# S7CAS-PLEIADES-CARTE-MERE_P07_DDR.net
KiCad netlist of a schematic drawn in Altium Designer
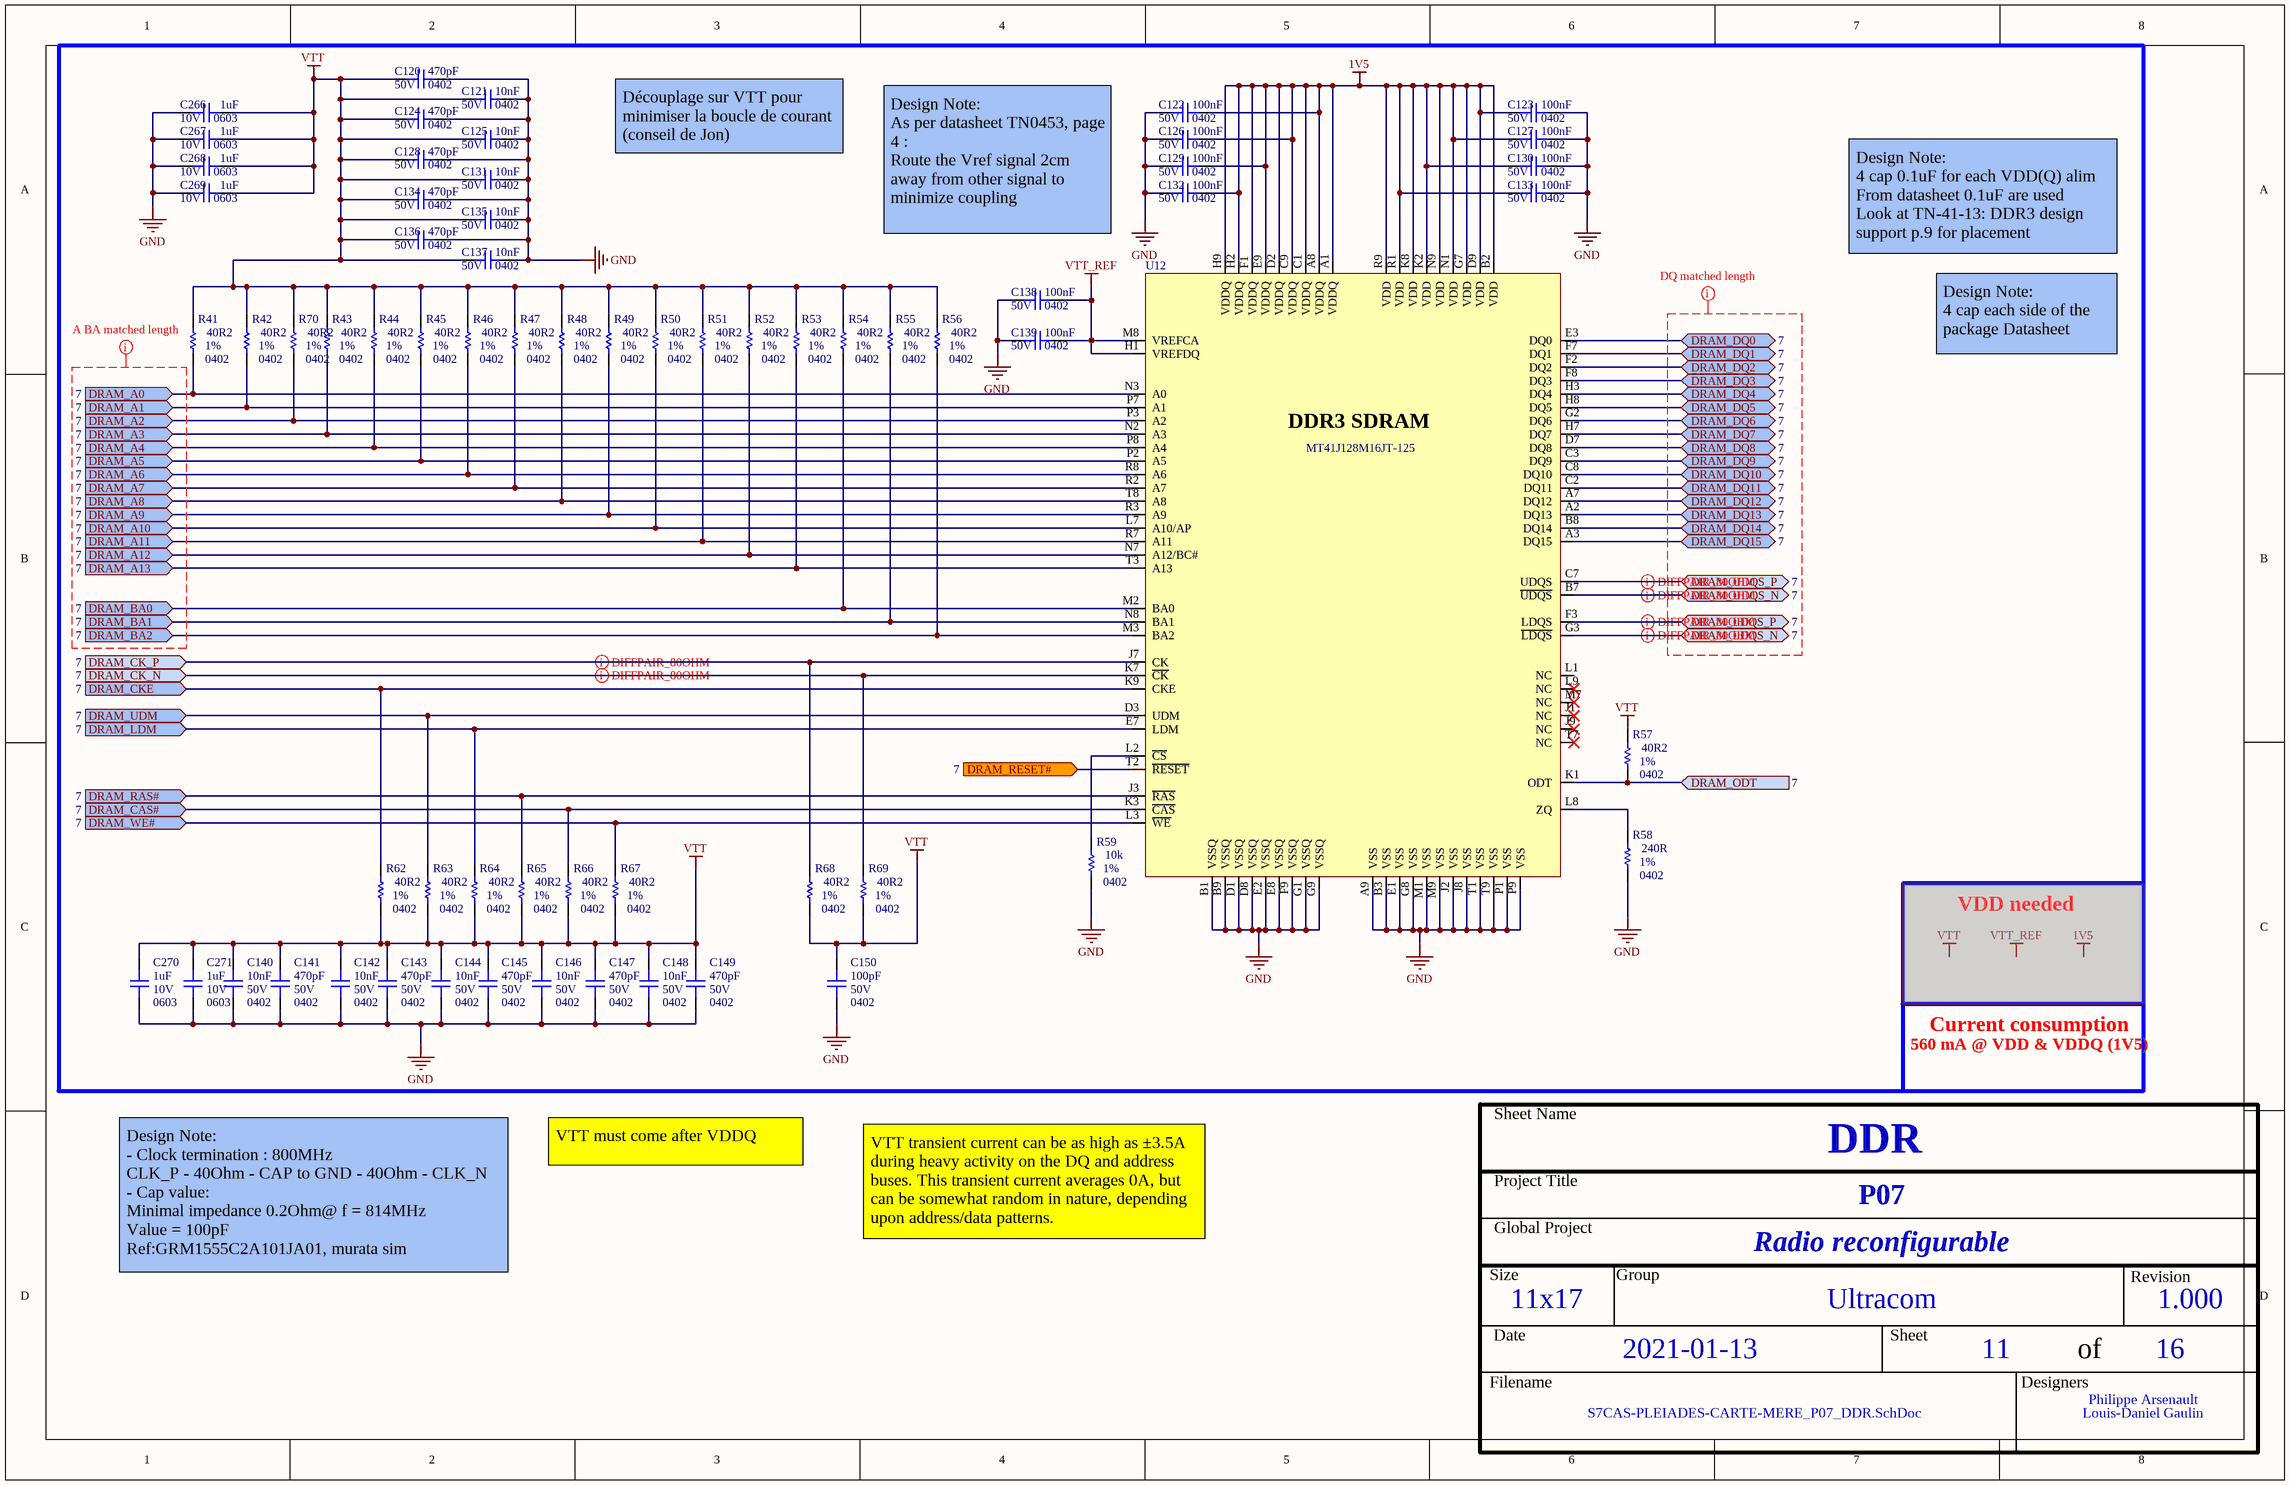
[diagram p0: S7CAS-PLEIADES-CARTE-MERE_P07_DDR.SchDoc]

(export (version "E")
  (design (tool "Eeschema 10.0.6"))
  (components
    (comp (ref "C120")
      (value "470pF")
      (footprint "CAP_0402")
      (description "CAP - 0402")
      (fields
        (field (name "VOLTAGE") "50V")
        (field (name "PACKAGE") "0402")
        (field (name "CREATEDBY") "Jonathan Bouchard")
      )
      (libsource (lib "S7CAS_LIB2021") (part "CAP - 0402"))
    )
    (comp (ref "C121")
      (value "10nF")
      (footprint "CAP_0402")
      (description "CAP - 0402")
      (fields
        (field (name "VOLTAGE") "50V")
        (field (name "PACKAGE") "0402")
        (field (name "CREATEDBY") "Jonathan Bouchard")
      )
      (libsource (lib "S7CAS_LIB2021") (part "CAP - 0402"))
    )
    (comp (ref "C122")
      (value "100nF")
      (footprint "CAP_0402")
      (description "CAP - 0402")
      (fields
        (field (name "VOLTAGE") "50V")
        (field (name "PACKAGE") "0402")
        (field (name "CREATEDBY") "Jonathan Bouchard")
      )
      (libsource (lib "S7CAS_LIB2021") (part "CAP - 0402"))
    )
    (comp (ref "C123")
      (value "100nF")
      (footprint "CAP_0402")
      (description "CAP - 0402")
      (fields
        (field (name "VOLTAGE") "50V")
        (field (name "PACKAGE") "0402")
        (field (name "CREATEDBY") "Jonathan Bouchard")
      )
      (libsource (lib "S7CAS_LIB2021") (part "CAP - 0402"))
    )
    (comp (ref "C124")
      (value "470pF")
      (footprint "CAP_0402")
      (description "CAP - 0402")
      (fields
        (field (name "VOLTAGE") "50V")
        (field (name "PACKAGE") "0402")
        (field (name "CREATEDBY") "Jonathan Bouchard")
      )
      (libsource (lib "S7CAS_LIB2021") (part "CAP - 0402"))
    )
    (comp (ref "C125")
      (value "10nF")
      (footprint "CAP_0402")
      (description "CAP - 0402")
      (fields
        (field (name "VOLTAGE") "50V")
        (field (name "PACKAGE") "0402")
        (field (name "CREATEDBY") "Jonathan Bouchard")
      )
      (libsource (lib "S7CAS_LIB2021") (part "CAP - 0402"))
    )
    (comp (ref "C126")
      (value "100nF")
      (footprint "CAP_0402")
      (description "CAP - 0402")
      (fields
        (field (name "VOLTAGE") "50V")
        (field (name "PACKAGE") "0402")
        (field (name "CREATEDBY") "Jonathan Bouchard")
      )
      (libsource (lib "S7CAS_LIB2021") (part "CAP - 0402"))
    )
    (comp (ref "C127")
      (value "100nF")
      (footprint "CAP_0402")
      (description "CAP - 0402")
      (fields
        (field (name "VOLTAGE") "50V")
        (field (name "PACKAGE") "0402")
        (field (name "CREATEDBY") "Jonathan Bouchard")
      )
      (libsource (lib "S7CAS_LIB2021") (part "CAP - 0402"))
    )
    (comp (ref "C128")
      (value "470pF")
      (footprint "CAP_0402")
      (description "CAP - 0402")
      (fields
        (field (name "VOLTAGE") "50V")
        (field (name "PACKAGE") "0402")
        (field (name "CREATEDBY") "Jonathan Bouchard")
      )
      (libsource (lib "S7CAS_LIB2021") (part "CAP - 0402"))
    )
    (comp (ref "C129")
      (value "100nF")
      (footprint "CAP_0402")
      (description "CAP - 0402")
      (fields
        (field (name "VOLTAGE") "50V")
        (field (name "PACKAGE") "0402")
        (field (name "CREATEDBY") "Jonathan Bouchard")
      )
      (libsource (lib "S7CAS_LIB2021") (part "CAP - 0402"))
    )
    (comp (ref "C130")
      (value "100nF")
      (footprint "CAP_0402")
      (description "CAP - 0402")
      (fields
        (field (name "VOLTAGE") "50V")
        (field (name "PACKAGE") "0402")
        (field (name "CREATEDBY") "Jonathan Bouchard")
      )
      (libsource (lib "S7CAS_LIB2021") (part "CAP - 0402"))
    )
    (comp (ref "C131")
      (value "10nF")
      (footprint "CAP_0402")
      (description "CAP - 0402")
      (fields
        (field (name "VOLTAGE") "50V")
        (field (name "PACKAGE") "0402")
        (field (name "CREATEDBY") "Jonathan Bouchard")
      )
      (libsource (lib "S7CAS_LIB2021") (part "CAP - 0402"))
    )
    (comp (ref "C132")
      (value "100nF")
      (footprint "CAP_0402")
      (description "CAP - 0402")
      (fields
        (field (name "VOLTAGE") "50V")
        (field (name "PACKAGE") "0402")
        (field (name "CREATEDBY") "Jonathan Bouchard")
      )
      (libsource (lib "S7CAS_LIB2021") (part "CAP - 0402"))
    )
    (comp (ref "C133")
      (value "100nF")
      (footprint "CAP_0402")
      (description "CAP - 0402")
      (fields
        (field (name "VOLTAGE") "50V")
        (field (name "PACKAGE") "0402")
        (field (name "CREATEDBY") "Jonathan Bouchard")
      )
      (libsource (lib "S7CAS_LIB2021") (part "CAP - 0402"))
    )
    (comp (ref "C134")
      (value "470pF")
      (footprint "CAP_0402")
      (description "CAP - 0402")
      (fields
        (field (name "VOLTAGE") "50V")
        (field (name "PACKAGE") "0402")
        (field (name "CREATEDBY") "Jonathan Bouchard")
      )
      (libsource (lib "S7CAS_LIB2021") (part "CAP - 0402"))
    )
    (comp (ref "C135")
      (value "10nF")
      (footprint "CAP_0402")
      (description "CAP - 0402")
      (fields
        (field (name "VOLTAGE") "50V")
        (field (name "PACKAGE") "0402")
        (field (name "CREATEDBY") "Jonathan Bouchard")
      )
      (libsource (lib "S7CAS_LIB2021") (part "CAP - 0402"))
    )
    (comp (ref "C136")
      (value "470pF")
      (footprint "CAP_0402")
      (description "CAP - 0402")
      (fields
        (field (name "VOLTAGE") "50V")
        (field (name "PACKAGE") "0402")
        (field (name "CREATEDBY") "Jonathan Bouchard")
      )
      (libsource (lib "S7CAS_LIB2021") (part "CAP - 0402"))
    )
    (comp (ref "C137")
      (value "10nF")
      (footprint "CAP_0402")
      (description "CAP - 0402")
      (fields
        (field (name "VOLTAGE") "50V")
        (field (name "PACKAGE") "0402")
        (field (name "CREATEDBY") "Jonathan Bouchard")
      )
      (libsource (lib "S7CAS_LIB2021") (part "CAP - 0402"))
    )
    (comp (ref "C138")
      (value "100nF")
      (footprint "CAP_0402")
      (description "CAP - 0402")
      (fields
        (field (name "VOLTAGE") "50V")
        (field (name "PACKAGE") "0402")
        (field (name "CREATEDBY") "Jonathan Bouchard")
      )
      (libsource (lib "S7CAS_LIB2021") (part "CAP - 0402"))
    )
    (comp (ref "C139")
      (value "100nF")
      (footprint "CAP_0402")
      (description "CAP - 0402")
      (fields
        (field (name "VOLTAGE") "50V")
        (field (name "PACKAGE") "0402")
        (field (name "CREATEDBY") "Jonathan Bouchard")
      )
      (libsource (lib "S7CAS_LIB2021") (part "CAP - 0402"))
    )
    (comp (ref "C140")
      (value "10nF")
      (footprint "CAP_0402")
      (description "CAP - 0402")
      (fields
        (field (name "VOLTAGE") "50V")
        (field (name "PACKAGE") "0402")
        (field (name "CREATEDBY") "Jonathan Bouchard")
      )
      (libsource (lib "S7CAS_LIB2021") (part "CAP - 0402"))
    )
    (comp (ref "C141")
      (value "470pF")
      (footprint "CAP_0402")
      (description "CAP - 0402")
      (fields
        (field (name "VOLTAGE") "50V")
        (field (name "PACKAGE") "0402")
        (field (name "CREATEDBY") "Jonathan Bouchard")
      )
      (libsource (lib "S7CAS_LIB2021") (part "CAP - 0402"))
    )
    (comp (ref "C142")
      (value "10nF")
      (footprint "CAP_0402")
      (description "CAP - 0402")
      (fields
        (field (name "VOLTAGE") "50V")
        (field (name "PACKAGE") "0402")
        (field (name "CREATEDBY") "Jonathan Bouchard")
      )
      (libsource (lib "S7CAS_LIB2021") (part "CAP - 0402"))
    )
    (comp (ref "C143")
      (value "470pF")
      (footprint "CAP_0402")
      (description "CAP - 0402")
      (fields
        (field (name "VOLTAGE") "50V")
        (field (name "PACKAGE") "0402")
        (field (name "CREATEDBY") "Jonathan Bouchard")
      )
      (libsource (lib "S7CAS_LIB2021") (part "CAP - 0402"))
    )
    (comp (ref "C144")
      (value "10nF")
      (footprint "CAP_0402")
      (description "CAP - 0402")
      (fields
        (field (name "VOLTAGE") "50V")
        (field (name "PACKAGE") "0402")
        (field (name "CREATEDBY") "Jonathan Bouchard")
      )
      (libsource (lib "S7CAS_LIB2021") (part "CAP - 0402"))
    )
    (comp (ref "C145")
      (value "470pF")
      (footprint "CAP_0402")
      (description "CAP - 0402")
      (fields
        (field (name "VOLTAGE") "50V")
        (field (name "PACKAGE") "0402")
        (field (name "CREATEDBY") "Jonathan Bouchard")
      )
      (libsource (lib "S7CAS_LIB2021") (part "CAP - 0402"))
    )
    (comp (ref "C146")
      (value "10nF")
      (footprint "CAP_0402")
      (description "CAP - 0402")
      (fields
        (field (name "VOLTAGE") "50V")
        (field (name "PACKAGE") "0402")
        (field (name "CREATEDBY") "Jonathan Bouchard")
      )
      (libsource (lib "S7CAS_LIB2021") (part "CAP - 0402"))
    )
    (comp (ref "C147")
      (value "470pF")
      (footprint "CAP_0402")
      (description "CAP - 0402")
      (fields
        (field (name "VOLTAGE") "50V")
        (field (name "PACKAGE") "0402")
        (field (name "CREATEDBY") "Jonathan Bouchard")
      )
      (libsource (lib "S7CAS_LIB2021") (part "CAP - 0402"))
    )
    (comp (ref "C148")
      (value "10nF")
      (footprint "CAP_0402")
      (description "CAP - 0402")
      (fields
        (field (name "VOLTAGE") "50V")
        (field (name "PACKAGE") "0402")
        (field (name "CREATEDBY") "Jonathan Bouchard")
      )
      (libsource (lib "S7CAS_LIB2021") (part "CAP - 0402"))
    )
    (comp (ref "C149")
      (value "470pF")
      (footprint "CAP_0402")
      (description "CAP - 0402")
      (fields
        (field (name "VOLTAGE") "50V")
        (field (name "PACKAGE") "0402")
        (field (name "CREATEDBY") "Jonathan Bouchard")
      )
      (libsource (lib "S7CAS_LIB2021") (part "CAP - 0402"))
    )
    (comp (ref "C150")
      (value "100pF")
      (footprint "CAP_0402")
      (description "CAP - 0402")
      (fields
        (field (name "VOLTAGE") "50V")
        (field (name "PACKAGE") "0402")
        (field (name "CREATEDBY") "Jonathan Bouchard")
      )
      (libsource (lib "S7CAS_LIB2021") (part "CAP - 0402"))
    )
    (comp (ref "C266")
      (value "1uF")
      (footprint "CAP_0603")
      (description "CAP - 0603")
      (fields
        (field (name "VOLTAGE") "10V")
        (field (name "PACKAGE") "0603")
        (field (name "CREATEDBY") "Jonathan Bouchard")
      )
      (libsource (lib "S7CAS_LIB2021") (part "CAP - 0603"))
    )
    (comp (ref "C267")
      (value "1uF")
      (footprint "CAP_0603")
      (description "CAP - 0603")
      (fields
        (field (name "VOLTAGE") "10V")
        (field (name "PACKAGE") "0603")
        (field (name "CREATEDBY") "Jonathan Bouchard")
      )
      (libsource (lib "S7CAS_LIB2021") (part "CAP - 0603"))
    )
    (comp (ref "C268")
      (value "1uF")
      (footprint "CAP_0603")
      (description "CAP - 0603")
      (fields
        (field (name "VOLTAGE") "10V")
        (field (name "PACKAGE") "0603")
        (field (name "CREATEDBY") "Jonathan Bouchard")
      )
      (libsource (lib "S7CAS_LIB2021") (part "CAP - 0603"))
    )
    (comp (ref "C269")
      (value "1uF")
      (footprint "CAP_0603")
      (description "CAP - 0603")
      (fields
        (field (name "VOLTAGE") "10V")
        (field (name "PACKAGE") "0603")
        (field (name "CREATEDBY") "Jonathan Bouchard")
      )
      (libsource (lib "S7CAS_LIB2021") (part "CAP - 0603"))
    )
    (comp (ref "C270")
      (value "1uF")
      (footprint "CAP_0603")
      (description "CAP - 0603")
      (fields
        (field (name "VOLTAGE") "10V")
        (field (name "PACKAGE") "0603")
        (field (name "CREATEDBY") "Jonathan Bouchard")
      )
      (libsource (lib "S7CAS_LIB2021") (part "CAP - 0603"))
    )
    (comp (ref "C271")
      (value "1uF")
      (footprint "CAP_0603")
      (description "CAP - 0603")
      (fields
        (field (name "VOLTAGE") "10V")
        (field (name "PACKAGE") "0603")
        (field (name "CREATEDBY") "Jonathan Bouchard")
      )
      (libsource (lib "S7CAS_LIB2021") (part "CAP - 0603"))
    )
    (comp (ref "R41")
      (value "40R2")
      (footprint "RES_0402")
      (description "RES - 0402")
      (fields
        (field (name "VOLTAGE") "50V")
        (field (name "POWER") "1/16W")
        (field (name "PACKAGE") "0402")
        (field (name "PRECISION") "1%")
        (field (name "CREATEDBY") "Jonathan Bouchard")
      )
      (libsource (lib "S7CAS_LIB2021") (part "RES - 0402"))
    )
    (comp (ref "R42")
      (value "40R2")
      (footprint "RES_0402")
      (description "RES - 0402")
      (fields
        (field (name "VOLTAGE") "50V")
        (field (name "POWER") "1/16W")
        (field (name "PACKAGE") "0402")
        (field (name "PRECISION") "1%")
        (field (name "CREATEDBY") "Jonathan Bouchard")
      )
      (libsource (lib "S7CAS_LIB2021") (part "RES - 0402"))
    )
    (comp (ref "R43")
      (value "40R2")
      (footprint "RES_0402")
      (description "RES - 0402")
      (fields
        (field (name "VOLTAGE") "50V")
        (field (name "POWER") "1/16W")
        (field (name "PACKAGE") "0402")
        (field (name "PRECISION") "1%")
        (field (name "CREATEDBY") "Jonathan Bouchard")
      )
      (libsource (lib "S7CAS_LIB2021") (part "RES - 0402"))
    )
    (comp (ref "R44")
      (value "40R2")
      (footprint "RES_0402")
      (description "RES - 0402")
      (fields
        (field (name "VOLTAGE") "50V")
        (field (name "POWER") "1/16W")
        (field (name "PACKAGE") "0402")
        (field (name "PRECISION") "1%")
        (field (name "CREATEDBY") "Jonathan Bouchard")
      )
      (libsource (lib "S7CAS_LIB2021") (part "RES - 0402"))
    )
    (comp (ref "R45")
      (value "40R2")
      (footprint "RES_0402")
      (description "RES - 0402")
      (fields
        (field (name "VOLTAGE") "50V")
        (field (name "POWER") "1/16W")
        (field (name "PACKAGE") "0402")
        (field (name "PRECISION") "1%")
        (field (name "CREATEDBY") "Jonathan Bouchard")
      )
      (libsource (lib "S7CAS_LIB2021") (part "RES - 0402"))
    )
    (comp (ref "R46")
      (value "40R2")
      (footprint "RES_0402")
      (description "RES - 0402")
      (fields
        (field (name "VOLTAGE") "50V")
        (field (name "POWER") "1/16W")
        (field (name "PACKAGE") "0402")
        (field (name "PRECISION") "1%")
        (field (name "CREATEDBY") "Jonathan Bouchard")
      )
      (libsource (lib "S7CAS_LIB2021") (part "RES - 0402"))
    )
    (comp (ref "R47")
      (value "40R2")
      (footprint "RES_0402")
      (description "RES - 0402")
      (fields
        (field (name "VOLTAGE") "50V")
        (field (name "POWER") "1/16W")
        (field (name "PACKAGE") "0402")
        (field (name "PRECISION") "1%")
        (field (name "CREATEDBY") "Jonathan Bouchard")
      )
      (libsource (lib "S7CAS_LIB2021") (part "RES - 0402"))
    )
    (comp (ref "R48")
      (value "40R2")
      (footprint "RES_0402")
      (description "RES - 0402")
      (fields
        (field (name "VOLTAGE") "50V")
        (field (name "POWER") "1/16W")
        (field (name "PACKAGE") "0402")
        (field (name "PRECISION") "1%")
        (field (name "CREATEDBY") "Jonathan Bouchard")
      )
      (libsource (lib "S7CAS_LIB2021") (part "RES - 0402"))
    )
    (comp (ref "R49")
      (value "40R2")
      (footprint "RES_0402")
      (description "RES - 0402")
      (fields
        (field (name "VOLTAGE") "50V")
        (field (name "POWER") "1/16W")
        (field (name "PACKAGE") "0402")
        (field (name "PRECISION") "1%")
        (field (name "CREATEDBY") "Jonathan Bouchard")
      )
      (libsource (lib "S7CAS_LIB2021") (part "RES - 0402"))
    )
    (comp (ref "R50")
      (value "40R2")
      (footprint "RES_0402")
      (description "RES - 0402")
      (fields
        (field (name "VOLTAGE") "50V")
        (field (name "POWER") "1/16W")
        (field (name "PACKAGE") "0402")
        (field (name "PRECISION") "1%")
        (field (name "CREATEDBY") "Jonathan Bouchard")
      )
      (libsource (lib "S7CAS_LIB2021") (part "RES - 0402"))
    )
    (comp (ref "R51")
      (value "40R2")
      (footprint "RES_0402")
      (description "RES - 0402")
      (fields
        (field (name "VOLTAGE") "50V")
        (field (name "POWER") "1/16W")
        (field (name "PACKAGE") "0402")
        (field (name "PRECISION") "1%")
        (field (name "CREATEDBY") "Jonathan Bouchard")
      )
      (libsource (lib "S7CAS_LIB2021") (part "RES - 0402"))
    )
    (comp (ref "R52")
      (value "40R2")
      (footprint "RES_0402")
      (description "RES - 0402")
      (fields
        (field (name "VOLTAGE") "50V")
        (field (name "POWER") "1/16W")
        (field (name "PACKAGE") "0402")
        (field (name "PRECISION") "1%")
        (field (name "CREATEDBY") "Jonathan Bouchard")
      )
      (libsource (lib "S7CAS_LIB2021") (part "RES - 0402"))
    )
    (comp (ref "R53")
      (value "40R2")
      (footprint "RES_0402")
      (description "RES - 0402")
      (fields
        (field (name "VOLTAGE") "50V")
        (field (name "POWER") "1/16W")
        (field (name "PACKAGE") "0402")
        (field (name "PRECISION") "1%")
        (field (name "CREATEDBY") "Jonathan Bouchard")
      )
      (libsource (lib "S7CAS_LIB2021") (part "RES - 0402"))
    )
    (comp (ref "R54")
      (value "40R2")
      (footprint "RES_0402")
      (description "RES - 0402")
      (fields
        (field (name "VOLTAGE") "50V")
        (field (name "POWER") "1/16W")
        (field (name "PACKAGE") "0402")
        (field (name "PRECISION") "1%")
        (field (name "CREATEDBY") "Jonathan Bouchard")
      )
      (libsource (lib "S7CAS_LIB2021") (part "RES - 0402"))
    )
    (comp (ref "R55")
      (value "40R2")
      (footprint "RES_0402")
      (description "RES - 0402")
      (fields
        (field (name "VOLTAGE") "50V")
        (field (name "POWER") "1/16W")
        (field (name "PACKAGE") "0402")
        (field (name "PRECISION") "1%")
        (field (name "CREATEDBY") "Jonathan Bouchard")
      )
      (libsource (lib "S7CAS_LIB2021") (part "RES - 0402"))
    )
    (comp (ref "R56")
      (value "40R2")
      (footprint "RES_0402")
      (description "RES - 0402")
      (fields
        (field (name "VOLTAGE") "50V")
        (field (name "POWER") "1/16W")
        (field (name "PACKAGE") "0402")
        (field (name "PRECISION") "1%")
        (field (name "CREATEDBY") "Jonathan Bouchard")
      )
      (libsource (lib "S7CAS_LIB2021") (part "RES - 0402"))
    )
    (comp (ref "R57")
      (value "40R2")
      (footprint "RES_0402")
      (description "RES - 0402")
      (fields
        (field (name "VOLTAGE") "50V")
        (field (name "POWER") "1/16W")
        (field (name "PACKAGE") "0402")
        (field (name "PRECISION") "1%")
        (field (name "CREATEDBY") "Jonathan Bouchard")
      )
      (libsource (lib "S7CAS_LIB2021") (part "RES - 0402"))
    )
    (comp (ref "R58")
      (value "240R")
      (footprint "RES_0402")
      (description "RES - 0402")
      (fields
        (field (name "VOLTAGE") "50V")
        (field (name "POWER") "1/16W")
        (field (name "PACKAGE") "0402")
        (field (name "PRECISION") "1%")
        (field (name "CREATEDBY") "Jonathan Bouchard")
      )
      (libsource (lib "S7CAS_LIB2021") (part "RES - 0402"))
    )
    (comp (ref "R59")
      (value "10k")
      (footprint "RES_0402")
      (description "RES - 0402")
      (fields
        (field (name "VOLTAGE") "50V")
        (field (name "POWER") "1/16W")
        (field (name "PACKAGE") "0402")
        (field (name "PRECISION") "1%")
        (field (name "CREATEDBY") "Jonathan Bouchard")
      )
      (libsource (lib "S7CAS_LIB2021") (part "RES - 0402"))
    )
    (comp (ref "R62")
      (value "40R2")
      (footprint "RES_0402")
      (description "RES - 0402")
      (fields
        (field (name "VOLTAGE") "50V")
        (field (name "POWER") "1/16W")
        (field (name "PACKAGE") "0402")
        (field (name "PRECISION") "1%")
        (field (name "CREATEDBY") "Jonathan Bouchard")
      )
      (libsource (lib "S7CAS_LIB2021") (part "RES - 0402"))
    )
    (comp (ref "R63")
      (value "40R2")
      (footprint "RES_0402")
      (description "RES - 0402")
      (fields
        (field (name "VOLTAGE") "50V")
        (field (name "POWER") "1/16W")
        (field (name "PACKAGE") "0402")
        (field (name "PRECISION") "1%")
        (field (name "CREATEDBY") "Jonathan Bouchard")
      )
      (libsource (lib "S7CAS_LIB2021") (part "RES - 0402"))
    )
    (comp (ref "R64")
      (value "40R2")
      (footprint "RES_0402")
      (description "RES - 0402")
      (fields
        (field (name "VOLTAGE") "50V")
        (field (name "POWER") "1/16W")
        (field (name "PACKAGE") "0402")
        (field (name "PRECISION") "1%")
        (field (name "CREATEDBY") "Jonathan Bouchard")
      )
      (libsource (lib "S7CAS_LIB2021") (part "RES - 0402"))
    )
    (comp (ref "R65")
      (value "40R2")
      (footprint "RES_0402")
      (description "RES - 0402")
      (fields
        (field (name "VOLTAGE") "50V")
        (field (name "POWER") "1/16W")
        (field (name "PACKAGE") "0402")
        (field (name "PRECISION") "1%")
        (field (name "CREATEDBY") "Jonathan Bouchard")
      )
      (libsource (lib "S7CAS_LIB2021") (part "RES - 0402"))
    )
    (comp (ref "R66")
      (value "40R2")
      (footprint "RES_0402")
      (description "RES - 0402")
      (fields
        (field (name "VOLTAGE") "50V")
        (field (name "POWER") "1/16W")
        (field (name "PACKAGE") "0402")
        (field (name "PRECISION") "1%")
        (field (name "CREATEDBY") "Jonathan Bouchard")
      )
      (libsource (lib "S7CAS_LIB2021") (part "RES - 0402"))
    )
    (comp (ref "R67")
      (value "40R2")
      (footprint "RES_0402")
      (description "RES - 0402")
      (fields
        (field (name "VOLTAGE") "50V")
        (field (name "POWER") "1/16W")
        (field (name "PACKAGE") "0402")
        (field (name "PRECISION") "1%")
        (field (name "CREATEDBY") "Jonathan Bouchard")
      )
      (libsource (lib "S7CAS_LIB2021") (part "RES - 0402"))
    )
    (comp (ref "R68")
      (value "40R2")
      (footprint "RES_0402")
      (description "RES - 0402")
      (fields
        (field (name "VOLTAGE") "50V")
        (field (name "POWER") "1/16W")
        (field (name "PACKAGE") "0402")
        (field (name "PRECISION") "1%")
        (field (name "CREATEDBY") "Jonathan Bouchard")
      )
      (libsource (lib "S7CAS_LIB2021") (part "RES - 0402"))
    )
    (comp (ref "R69")
      (value "40R2")
      (footprint "RES_0402")
      (description "RES - 0402")
      (fields
        (field (name "VOLTAGE") "50V")
        (field (name "POWER") "1/16W")
        (field (name "PACKAGE") "0402")
        (field (name "PRECISION") "1%")
        (field (name "CREATEDBY") "Jonathan Bouchard")
      )
      (libsource (lib "S7CAS_LIB2021") (part "RES - 0402"))
    )
    (comp (ref "R70")
      (value "40R2")
      (footprint "RES_0402")
      (description "RES - 0402")
      (fields
        (field (name "VOLTAGE") "50V")
        (field (name "POWER") "1/16W")
        (field (name "PACKAGE") "0402")
        (field (name "PRECISION") "1%")
        (field (name "CREATEDBY") "Jonathan Bouchard")
      )
      (libsource (lib "S7CAS_LIB2021") (part "RES - 0402"))
    )
    (comp (ref "U12")
      (value "MT41J128M16JT-125")
      (footprint "MEM_DDR3_MT41J128M16JT-125")
      (description "MEM - DDR3 SDRAM 2GBIT 800MHZ - TFBGA-96")
      (fields
        (field (name "VOLTAGE") "1.425 V ~ 1.575 V")
        (field (name "MFG") "Micrel")
        (field (name "CREATEDBY") "Jonathan Bouchard")
      )
      (libsource (lib "S7CAS_LIB2021") (part "MEM_DDR3_MT41J128M16JT-125{colon}K TR"))
    )
  )
  (nets
    (net (code "1") (name "/DRAM_A0") (class "Default")
      (node (ref "R41") (pin "1") (pinfunction "1_1") (pintype "passive"))
      (node (ref "U12") (pin "N3") (pinfunction "A0_N3") (pintype "passive"))
    )
    (net (code "2") (name "/DRAM_A1") (class "Default")
      (node (ref "R42") (pin "1") (pinfunction "1_1") (pintype "passive"))
      (node (ref "U12") (pin "P7") (pinfunction "A1_P7") (pintype "passive"))
    )
    (net (code "3") (name "/DRAM_A2") (class "Default")
      (node (ref "R70") (pin "1") (pinfunction "1_1") (pintype "passive"))
      (node (ref "U12") (pin "P3") (pinfunction "A2_P3") (pintype "passive"))
    )
    (net (code "4") (name "/DRAM_A3") (class "Default")
      (node (ref "R43") (pin "1") (pinfunction "1_1") (pintype "passive"))
      (node (ref "U12") (pin "N2") (pinfunction "A3_N2") (pintype "passive"))
    )
    (net (code "5") (name "/DRAM_A4") (class "Default")
      (node (ref "R44") (pin "1") (pinfunction "1_1") (pintype "passive"))
      (node (ref "U12") (pin "P8") (pinfunction "A4_P8") (pintype "passive"))
    )
    (net (code "6") (name "/DRAM_A5") (class "Default")
      (node (ref "R45") (pin "1") (pinfunction "1_1") (pintype "passive"))
      (node (ref "U12") (pin "P2") (pinfunction "A5_P2") (pintype "passive"))
    )
    (net (code "7") (name "/DRAM_A6") (class "Default")
      (node (ref "R46") (pin "1") (pinfunction "1_1") (pintype "passive"))
      (node (ref "U12") (pin "R8") (pinfunction "A6_R8") (pintype "passive"))
    )
    (net (code "8") (name "/DRAM_A7") (class "Default")
      (node (ref "R47") (pin "1") (pinfunction "1_1") (pintype "passive"))
      (node (ref "U12") (pin "R2") (pinfunction "A7_R2") (pintype "passive"))
    )
    (net (code "9") (name "/DRAM_A8") (class "Default")
      (node (ref "R48") (pin "1") (pinfunction "1_1") (pintype "passive"))
      (node (ref "U12") (pin "T8") (pinfunction "A8_T8") (pintype "passive"))
    )
    (net (code "10") (name "/DRAM_A9") (class "Default")
      (node (ref "R49") (pin "1") (pinfunction "1_1") (pintype "passive"))
      (node (ref "U12") (pin "R3") (pinfunction "A9_R3") (pintype "passive"))
    )
    (net (code "11") (name "/DRAM_A10") (class "Default")
      (node (ref "R50") (pin "1") (pinfunction "1_1") (pintype "passive"))
      (node (ref "U12") (pin "L7") (pinfunction "A10/AP_L7") (pintype "passive"))
    )
    (net (code "12") (name "/DRAM_A11") (class "Default")
      (node (ref "R51") (pin "1") (pinfunction "1_1") (pintype "passive"))
      (node (ref "U12") (pin "R7") (pinfunction "A11_R7") (pintype "passive"))
    )
    (net (code "13") (name "/DRAM_A12") (class "Default")
      (node (ref "R52") (pin "1") (pinfunction "1_1") (pintype "passive"))
      (node (ref "U12") (pin "N7") (pinfunction "A12/BC#_N7") (pintype "passive"))
    )
    (net (code "14") (name "/DRAM_A13") (class "Default")
      (node (ref "R53") (pin "1") (pinfunction "1_1") (pintype "passive"))
      (node (ref "U12") (pin "T3") (pinfunction "A13_T3") (pintype "passive"))
    )
    (net (code "15") (name "/DRAM_BA0") (class "Default")
      (node (ref "R54") (pin "1") (pinfunction "1_1") (pintype "passive"))
      (node (ref "U12") (pin "M2") (pinfunction "BA0_M2") (pintype "passive"))
    )
    (net (code "16") (name "/DRAM_BA1") (class "Default")
      (node (ref "R55") (pin "1") (pinfunction "1_1") (pintype "passive"))
      (node (ref "U12") (pin "N8") (pinfunction "BA1_N8") (pintype "passive"))
    )
    (net (code "17") (name "/DRAM_BA2") (class "Default")
      (node (ref "R56") (pin "1") (pinfunction "1_1") (pintype "passive"))
      (node (ref "U12") (pin "M3") (pinfunction "BA2_M3") (pintype "passive"))
    )
    (net (code "18") (name "/DRAM_CAS#") (class "Default")
      (node (ref "R66") (pin "2") (pinfunction "2_2") (pintype "passive"))
      (node (ref "U12") (pin "K3") (pinfunction "CAS_K3") (pintype "passive"))
    )
    (net (code "19") (name "/DRAM_CKE") (class "Default")
      (node (ref "R62") (pin "2") (pinfunction "2_2") (pintype "passive"))
      (node (ref "U12") (pin "K9") (pinfunction "CKE_K9") (pintype "passive"))
    )
    (net (code "20") (name "/DRAM_CK_N") (class "Default")
      (node (ref "R69") (pin "2") (pinfunction "2_2") (pintype "passive"))
      (node (ref "U12") (pin "K7") (pinfunction "CK_K7") (pintype "passive"))
    )
    (net (code "21") (name "/DRAM_CK_P") (class "Default")
      (node (ref "R68") (pin "2") (pinfunction "2_2") (pintype "passive"))
      (node (ref "U12") (pin "J7") (pinfunction "CK_J7") (pintype "passive"))
    )
    (net (code "22") (name "/DRAM_DQ0") (class "Default")
      (node (ref "U12") (pin "E3") (pinfunction "DQ0_E3") (pintype "passive"))
    )
    (net (code "23") (name "/DRAM_DQ1") (class "Default")
      (node (ref "U12") (pin "F7") (pinfunction "DQ1_F7") (pintype "passive"))
    )
    (net (code "24") (name "/DRAM_DQ2") (class "Default")
      (node (ref "U12") (pin "F2") (pinfunction "DQ2_F2") (pintype "passive"))
    )
    (net (code "25") (name "/DRAM_DQ3") (class "Default")
      (node (ref "U12") (pin "F8") (pinfunction "DQ3_F8") (pintype "passive"))
    )
    (net (code "26") (name "/DRAM_DQ4") (class "Default")
      (node (ref "U12") (pin "H3") (pinfunction "DQ4_H3") (pintype "passive"))
    )
    (net (code "27") (name "/DRAM_DQ5") (class "Default")
      (node (ref "U12") (pin "H8") (pinfunction "DQ5_H8") (pintype "passive"))
    )
    (net (code "28") (name "/DRAM_DQ6") (class "Default")
      (node (ref "U12") (pin "G2") (pinfunction "DQ6_G2") (pintype "passive"))
    )
    (net (code "29") (name "/DRAM_DQ7") (class "Default")
      (node (ref "U12") (pin "H7") (pinfunction "DQ7_H7") (pintype "passive"))
    )
    (net (code "30") (name "/DRAM_DQ8") (class "Default")
      (node (ref "U12") (pin "D7") (pinfunction "DQ8_D7") (pintype "passive"))
    )
    (net (code "31") (name "/DRAM_DQ9") (class "Default")
      (node (ref "U12") (pin "C3") (pinfunction "DQ9_C3") (pintype "passive"))
    )
    (net (code "32") (name "/DRAM_DQ10") (class "Default")
      (node (ref "U12") (pin "C8") (pinfunction "DQ10_C8") (pintype "passive"))
    )
    (net (code "33") (name "/DRAM_DQ11") (class "Default")
      (node (ref "U12") (pin "C2") (pinfunction "DQ11_C2") (pintype "passive"))
    )
    (net (code "34") (name "/DRAM_DQ12") (class "Default")
      (node (ref "U12") (pin "A7") (pinfunction "DQ12_A7") (pintype "passive"))
    )
    (net (code "35") (name "/DRAM_DQ13") (class "Default")
      (node (ref "U12") (pin "A2") (pinfunction "DQ13_A2") (pintype "passive"))
    )
    (net (code "36") (name "/DRAM_DQ14") (class "Default")
      (node (ref "U12") (pin "B8") (pinfunction "DQ14_B8") (pintype "passive"))
    )
    (net (code "37") (name "/DRAM_DQ15") (class "Default")
      (node (ref "U12") (pin "A3") (pinfunction "DQ15_A3") (pintype "passive"))
    )
    (net (code "38") (name "/DRAM_LDM") (class "Default")
      (node (ref "R64") (pin "2") (pinfunction "2_2") (pintype "passive"))
      (node (ref "U12") (pin "E7") (pinfunction "LDM_E7") (pintype "passive"))
    )
    (net (code "39") (name "/DRAM_LDQS_N") (class "Default")
      (node (ref "U12") (pin "G3") (pinfunction "LDQS_G3") (pintype "passive"))
    )
    (net (code "40") (name "/DRAM_LDQS_P") (class "Default")
      (node (ref "U12") (pin "F3") (pinfunction "LDQS_F3") (pintype "passive"))
    )
    (net (code "41") (name "/DRAM_ODT") (class "Default")
      (node (ref "R57") (pin "1") (pinfunction "1_1") (pintype "passive"))
      (node (ref "U12") (pin "K1") (pinfunction "ODT_K1") (pintype "passive"))
    )
    (net (code "42") (name "/DRAM_RAS#") (class "Default")
      (node (ref "R65") (pin "2") (pinfunction "2_2") (pintype "passive"))
      (node (ref "U12") (pin "J3") (pinfunction "RAS_J3") (pintype "passive"))
    )
    (net (code "43") (name "/DRAM_RESET#") (class "Default")
      (node (ref "U12") (pin "T2") (pinfunction "RESET_T2") (pintype "passive"))
    )
    (net (code "44") (name "/DRAM_UDM") (class "Default")
      (node (ref "R63") (pin "2") (pinfunction "2_2") (pintype "passive"))
      (node (ref "U12") (pin "D3") (pinfunction "UDM_D3") (pintype "passive"))
    )
    (net (code "45") (name "/DRAM_UDQS_N") (class "Default")
      (node (ref "U12") (pin "B7") (pinfunction "UDQS_B7") (pintype "passive"))
    )
    (net (code "46") (name "/DRAM_UDQS_P") (class "Default")
      (node (ref "U12") (pin "C7") (pinfunction "UDQS_C7") (pintype "passive"))
    )
    (net (code "47") (name "/DRAM_WE#") (class "Default")
      (node (ref "R67") (pin "2") (pinfunction "2_2") (pintype "passive"))
      (node (ref "U12") (pin "L3") (pinfunction "WE_L3") (pintype "passive"))
    )
    (net (code "48") (name "1V5") (class "Default")
      (node (ref "C122") (pin "1") (pinfunction "1_1") (pintype "passive"))
      (node (ref "C123") (pin "2") (pinfunction "2_2") (pintype "passive"))
      (node (ref "C126") (pin "1") (pinfunction "1_1") (pintype "passive"))
      (node (ref "C127") (pin "2") (pinfunction "2_2") (pintype "passive"))
      (node (ref "C129") (pin "1") (pinfunction "1_1") (pintype "passive"))
      (node (ref "C130") (pin "2") (pinfunction "2_2") (pintype "passive"))
      (node (ref "C132") (pin "1") (pinfunction "1_1") (pintype "passive"))
      (node (ref "C133") (pin "2") (pinfunction "2_2") (pintype "passive"))
      (node (ref "U12") (pin "A1") (pinfunction "VDDQ_A1") (pintype "power_in"))
      (node (ref "U12") (pin "A8") (pinfunction "VDDQ_A8") (pintype "power_in"))
      (node (ref "U12") (pin "B2") (pinfunction "VDD_B2") (pintype "power_in"))
      (node (ref "U12") (pin "C1") (pinfunction "VDDQ_C1") (pintype "power_in"))
      (node (ref "U12") (pin "C9") (pinfunction "VDDQ_C9") (pintype "power_in"))
      (node (ref "U12") (pin "D2") (pinfunction "VDDQ_D2") (pintype "power_in"))
      (node (ref "U12") (pin "D9") (pinfunction "VDD_D9") (pintype "power_in"))
      (node (ref "U12") (pin "E9") (pinfunction "VDDQ_E9") (pintype "power_in"))
      (node (ref "U12") (pin "F1") (pinfunction "VDDQ_F1") (pintype "power_in"))
      (node (ref "U12") (pin "G7") (pinfunction "VDD_G7") (pintype "power_in"))
      (node (ref "U12") (pin "H2") (pinfunction "VDDQ_H2") (pintype "power_in"))
      (node (ref "U12") (pin "H9") (pinfunction "VDDQ_H9") (pintype "power_in"))
      (node (ref "U12") (pin "K2") (pinfunction "VDD_K2") (pintype "power_in"))
      (node (ref "U12") (pin "K8") (pinfunction "VDD_K8") (pintype "power_in"))
      (node (ref "U12") (pin "N1") (pinfunction "VDD_N1") (pintype "power_in"))
      (node (ref "U12") (pin "N9") (pinfunction "VDD_N9") (pintype "power_in"))
      (node (ref "U12") (pin "R1") (pinfunction "VDD_R1") (pintype "power_in"))
      (node (ref "U12") (pin "R9") (pinfunction "VDD_R9") (pintype "power_in"))
    )
    (net (code "49") (name "GND") (class "Default")
      (node (ref "C120") (pin "1") (pinfunction "1_1") (pintype "passive"))
      (node (ref "C121") (pin "1") (pinfunction "1_1") (pintype "passive"))
      (node (ref "C122") (pin "2") (pinfunction "2_2") (pintype "passive"))
      (node (ref "C123") (pin "1") (pinfunction "1_1") (pintype "passive"))
      (node (ref "C124") (pin "1") (pinfunction "1_1") (pintype "passive"))
      (node (ref "C125") (pin "1") (pinfunction "1_1") (pintype "passive"))
      (node (ref "C126") (pin "2") (pinfunction "2_2") (pintype "passive"))
      (node (ref "C127") (pin "1") (pinfunction "1_1") (pintype "passive"))
      (node (ref "C128") (pin "1") (pinfunction "1_1") (pintype "passive"))
      (node (ref "C129") (pin "2") (pinfunction "2_2") (pintype "passive"))
      (node (ref "C130") (pin "1") (pinfunction "1_1") (pintype "passive"))
      (node (ref "C131") (pin "1") (pinfunction "1_1") (pintype "passive"))
      (node (ref "C132") (pin "2") (pinfunction "2_2") (pintype "passive"))
      (node (ref "C133") (pin "1") (pinfunction "1_1") (pintype "passive"))
      (node (ref "C134") (pin "1") (pinfunction "1_1") (pintype "passive"))
      (node (ref "C135") (pin "1") (pinfunction "1_1") (pintype "passive"))
      (node (ref "C136") (pin "1") (pinfunction "1_1") (pintype "passive"))
      (node (ref "C137") (pin "1") (pinfunction "1_1") (pintype "passive"))
      (node (ref "C138") (pin "2") (pinfunction "2_2") (pintype "passive"))
      (node (ref "C139") (pin "2") (pinfunction "2_2") (pintype "passive"))
      (node (ref "C140") (pin "1") (pinfunction "1_1") (pintype "passive"))
      (node (ref "C141") (pin "1") (pinfunction "1_1") (pintype "passive"))
      (node (ref "C142") (pin "1") (pinfunction "1_1") (pintype "passive"))
      (node (ref "C143") (pin "1") (pinfunction "1_1") (pintype "passive"))
      (node (ref "C144") (pin "1") (pinfunction "1_1") (pintype "passive"))
      (node (ref "C145") (pin "1") (pinfunction "1_1") (pintype "passive"))
      (node (ref "C146") (pin "1") (pinfunction "1_1") (pintype "passive"))
      (node (ref "C147") (pin "1") (pinfunction "1_1") (pintype "passive"))
      (node (ref "C148") (pin "1") (pinfunction "1_1") (pintype "passive"))
      (node (ref "C149") (pin "1") (pinfunction "1_1") (pintype "passive"))
      (node (ref "C150") (pin "1") (pinfunction "1_1") (pintype "passive"))
      (node (ref "C266") (pin "2") (pinfunction "2_2") (pintype "passive"))
      (node (ref "C267") (pin "2") (pinfunction "2_2") (pintype "passive"))
      (node (ref "C268") (pin "2") (pinfunction "2_2") (pintype "passive"))
      (node (ref "C269") (pin "2") (pinfunction "2_2") (pintype "passive"))
      (node (ref "C270") (pin "1") (pinfunction "1_1") (pintype "passive"))
      (node (ref "C271") (pin "1") (pinfunction "1_1") (pintype "passive"))
      (node (ref "R58") (pin "1") (pinfunction "1_1") (pintype "passive"))
      (node (ref "R59") (pin "1") (pinfunction "1_1") (pintype "passive"))
      (node (ref "U12") (pin "A9") (pinfunction "VSS_A9") (pintype "passive"))
      (node (ref "U12") (pin "B1") (pinfunction "VSSQ_B1") (pintype "passive"))
      (node (ref "U12") (pin "B3") (pinfunction "VSS_B3") (pintype "passive"))
      (node (ref "U12") (pin "B9") (pinfunction "VSSQ_B9") (pintype "passive"))
      (node (ref "U12") (pin "D1") (pinfunction "VSSQ_D1") (pintype "passive"))
      (node (ref "U12") (pin "D8") (pinfunction "VSSQ_D8") (pintype "passive"))
      (node (ref "U12") (pin "E1") (pinfunction "VSS_E1") (pintype "passive"))
      (node (ref "U12") (pin "E2") (pinfunction "VSSQ_E2") (pintype "passive"))
      (node (ref "U12") (pin "E8") (pinfunction "VSSQ_E8") (pintype "passive"))
      (node (ref "U12") (pin "F9") (pinfunction "VSSQ_F9") (pintype "passive"))
      (node (ref "U12") (pin "G1") (pinfunction "VSSQ_G1") (pintype "passive"))
      (node (ref "U12") (pin "G8") (pinfunction "VSS_G8") (pintype "passive"))
      (node (ref "U12") (pin "G9") (pinfunction "VSSQ_G9") (pintype "passive"))
      (node (ref "U12") (pin "J2") (pinfunction "VSS_J2") (pintype "passive"))
      (node (ref "U12") (pin "J8") (pinfunction "VSS_J8") (pintype "passive"))
      (node (ref "U12") (pin "M1") (pinfunction "VSS_M1") (pintype "passive"))
      (node (ref "U12") (pin "M9") (pinfunction "VSS_M9") (pintype "passive"))
      (node (ref "U12") (pin "P1") (pinfunction "VSS_P1") (pintype "passive"))
      (node (ref "U12") (pin "P9") (pinfunction "VSS_P9") (pintype "passive"))
      (node (ref "U12") (pin "T1") (pinfunction "VSS_T1") (pintype "passive"))
      (node (ref "U12") (pin "T9") (pinfunction "VSS_T9") (pintype "passive"))
    )
    (net (code "50") (name "Net-(U12-CS)") (class "Default")
      (node (ref "R59") (pin "2") (pinfunction "2_2") (pintype "passive"))
      (node (ref "U12") (pin "L2") (pinfunction "CS_L2") (pintype "passive"))
    )
    (net (code "51") (name "Net-(U12-ZQ)") (class "Default")
      (node (ref "R58") (pin "2") (pinfunction "2_2") (pintype "passive"))
      (node (ref "U12") (pin "L8") (pinfunction "ZQ_L8") (pintype "passive"))
    )
    (net (code "52") (name "VTT") (class "Default")
      (node (ref "C120") (pin "2") (pinfunction "2_2") (pintype "passive"))
      (node (ref "C121") (pin "2") (pinfunction "2_2") (pintype "passive"))
      (node (ref "C124") (pin "2") (pinfunction "2_2") (pintype "passive"))
      (node (ref "C125") (pin "2") (pinfunction "2_2") (pintype "passive"))
      (node (ref "C128") (pin "2") (pinfunction "2_2") (pintype "passive"))
      (node (ref "C131") (pin "2") (pinfunction "2_2") (pintype "passive"))
      (node (ref "C134") (pin "2") (pinfunction "2_2") (pintype "passive"))
      (node (ref "C135") (pin "2") (pinfunction "2_2") (pintype "passive"))
      (node (ref "C136") (pin "2") (pinfunction "2_2") (pintype "passive"))
      (node (ref "C137") (pin "2") (pinfunction "2_2") (pintype "passive"))
      (node (ref "C140") (pin "2") (pinfunction "2_2") (pintype "passive"))
      (node (ref "C141") (pin "2") (pinfunction "2_2") (pintype "passive"))
      (node (ref "C142") (pin "2") (pinfunction "2_2") (pintype "passive"))
      (node (ref "C143") (pin "2") (pinfunction "2_2") (pintype "passive"))
      (node (ref "C144") (pin "2") (pinfunction "2_2") (pintype "passive"))
      (node (ref "C145") (pin "2") (pinfunction "2_2") (pintype "passive"))
      (node (ref "C146") (pin "2") (pinfunction "2_2") (pintype "passive"))
      (node (ref "C147") (pin "2") (pinfunction "2_2") (pintype "passive"))
      (node (ref "C148") (pin "2") (pinfunction "2_2") (pintype "passive"))
      (node (ref "C149") (pin "2") (pinfunction "2_2") (pintype "passive"))
      (node (ref "C150") (pin "2") (pinfunction "2_2") (pintype "passive"))
      (node (ref "C266") (pin "1") (pinfunction "1_1") (pintype "passive"))
      (node (ref "C267") (pin "1") (pinfunction "1_1") (pintype "passive"))
      (node (ref "C268") (pin "1") (pinfunction "1_1") (pintype "passive"))
      (node (ref "C269") (pin "1") (pinfunction "1_1") (pintype "passive"))
      (node (ref "C270") (pin "2") (pinfunction "2_2") (pintype "passive"))
      (node (ref "C271") (pin "2") (pinfunction "2_2") (pintype "passive"))
      (node (ref "R41") (pin "2") (pinfunction "2_2") (pintype "passive"))
      (node (ref "R42") (pin "2") (pinfunction "2_2") (pintype "passive"))
      (node (ref "R43") (pin "2") (pinfunction "2_2") (pintype "passive"))
      (node (ref "R44") (pin "2") (pinfunction "2_2") (pintype "passive"))
      (node (ref "R45") (pin "2") (pinfunction "2_2") (pintype "passive"))
      (node (ref "R46") (pin "2") (pinfunction "2_2") (pintype "passive"))
      (node (ref "R47") (pin "2") (pinfunction "2_2") (pintype "passive"))
      (node (ref "R48") (pin "2") (pinfunction "2_2") (pintype "passive"))
      (node (ref "R49") (pin "2") (pinfunction "2_2") (pintype "passive"))
      (node (ref "R50") (pin "2") (pinfunction "2_2") (pintype "passive"))
      (node (ref "R51") (pin "2") (pinfunction "2_2") (pintype "passive"))
      (node (ref "R52") (pin "2") (pinfunction "2_2") (pintype "passive"))
      (node (ref "R53") (pin "2") (pinfunction "2_2") (pintype "passive"))
      (node (ref "R54") (pin "2") (pinfunction "2_2") (pintype "passive"))
      (node (ref "R55") (pin "2") (pinfunction "2_2") (pintype "passive"))
      (node (ref "R56") (pin "2") (pinfunction "2_2") (pintype "passive"))
      (node (ref "R57") (pin "2") (pinfunction "2_2") (pintype "passive"))
      (node (ref "R62") (pin "1") (pinfunction "1_1") (pintype "passive"))
      (node (ref "R63") (pin "1") (pinfunction "1_1") (pintype "passive"))
      (node (ref "R64") (pin "1") (pinfunction "1_1") (pintype "passive"))
      (node (ref "R65") (pin "1") (pinfunction "1_1") (pintype "passive"))
      (node (ref "R66") (pin "1") (pinfunction "1_1") (pintype "passive"))
      (node (ref "R67") (pin "1") (pinfunction "1_1") (pintype "passive"))
      (node (ref "R68") (pin "1") (pinfunction "1_1") (pintype "passive"))
      (node (ref "R69") (pin "1") (pinfunction "1_1") (pintype "passive"))
      (node (ref "R70") (pin "2") (pinfunction "2_2") (pintype "passive"))
    )
    (net (code "53") (name "VTT_REF") (class "Default")
      (node (ref "C138") (pin "1") (pinfunction "1_1") (pintype "passive"))
      (node (ref "C139") (pin "1") (pinfunction "1_1") (pintype "passive"))
      (node (ref "U12") (pin "H1") (pinfunction "VREFDQ_H1") (pintype "power_in"))
      (node (ref "U12") (pin "M8") (pinfunction "VREFCA_M8") (pintype "power_in"))
    )
    (net (code "54") (name "unconnected-(U12-NC-PadJ1)") (class "Default")
      (node (ref "U12") (pin "J1") (pinfunction "NC_J1") (pintype "passive+no_connect"))
    )
    (net (code "55") (name "unconnected-(U12-NC-PadJ9)") (class "Default")
      (node (ref "U12") (pin "J9") (pinfunction "NC_J9") (pintype "passive+no_connect"))
    )
    (net (code "56") (name "unconnected-(U12-NC-PadL1)") (class "Default")
      (node (ref "U12") (pin "L1") (pinfunction "NC_L1") (pintype "passive"))
    )
    (net (code "57") (name "unconnected-(U12-NC-PadL9)") (class "Default")
      (node (ref "U12") (pin "L9") (pinfunction "NC_L9") (pintype "passive+no_connect"))
    )
    (net (code "58") (name "unconnected-(U12-NC-PadM7)") (class "Default")
      (node (ref "U12") (pin "M7") (pinfunction "NC_M7") (pintype "passive+no_connect"))
    )
    (net (code "59") (name "unconnected-(U12-NC-PadT7)") (class "Default")
      (node (ref "U12") (pin "T7") (pinfunction "NC_T7") (pintype "passive+no_connect"))
    )
  )
)
